# Current_Sensor_Breakout.net
KiCad netlist of a schematic drawn in Altium Designer
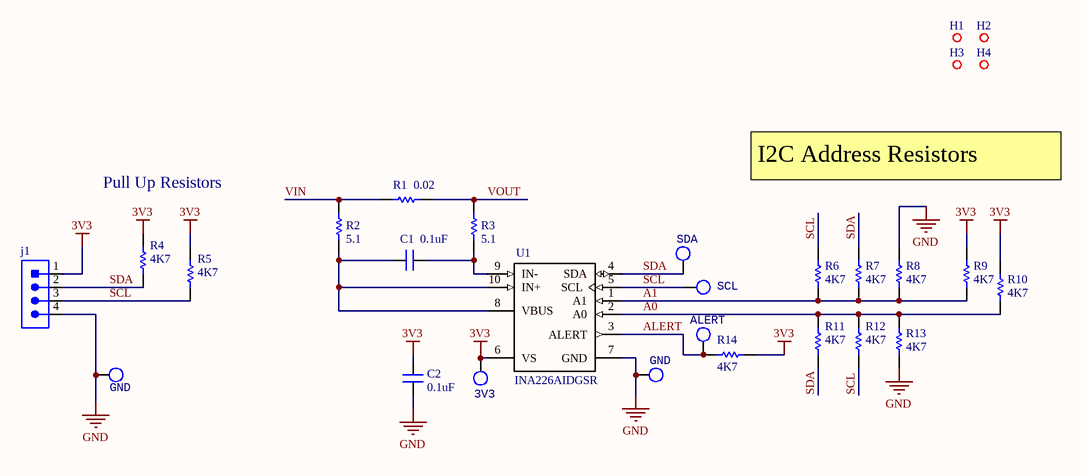
[diagram p0: Current Sensor Breakout.SchDoc]

(export (version "E")
  (design (tool "Eeschema 10.0.6"))
  (components
    (comp (ref "C1")
      (value "0.1uF")
      (footprint "CAPC2012X140N")
      (description "CAP CER 0.1UF 50V X7R 0805")
      (fields (field (name "TOLERANCE") "10%") (field (name "Comment") "CAP_0.1uF_50V_0805"))
      (libsource (lib "UWRT_Schematic_Library_2020") (part "CAP_0.1uF_50V_0805"))
    )
    (comp (ref "C2")
      (value "0.1uF")
      (footprint "CAPC2012X140N")
      (description "CAP CER 0.1UF 50V X7R 0805")
      (fields (field (name "TOLERANCE") "10%") (field (name "Comment") "CAP_0.1uF_50V_0805"))
      (libsource (lib "UWRT_Schematic_Library_2020") (part "CAP_0.1uF_50V_0805"))
    )
    (comp (ref "H1")
      (value "MOUNTING_HOLES")
      (footprint "MOUNTING_HOLE")
      (description "6cm x 6cm")
      (libsource (lib "UWRT_Schematic_Library_2020") (part "MOUNTING_HOLES"))
    )
    (comp (ref "H2")
      (value "MOUNTING_HOLES")
      (footprint "MOUNTING_HOLE")
      (description "6cm x 6cm")
      (libsource (lib "UWRT_Schematic_Library_2020") (part "MOUNTING_HOLES"))
    )
    (comp (ref "H3")
      (value "MOUNTING_HOLES")
      (footprint "MOUNTING_HOLE")
      (description "6cm x 6cm")
      (libsource (lib "UWRT_Schematic_Library_2020") (part "MOUNTING_HOLES"))
    )
    (comp (ref "H4")
      (value "MOUNTING_HOLES")
      (footprint "MOUNTING_HOLE")
      (description "6cm x 6cm")
      (libsource (lib "UWRT_Schematic_Library_2020") (part "MOUNTING_HOLES"))
    )
    (comp (ref "j1")
      (value "CON_4M_TERM")
      (footprint "UWRT_Footprint_Library_2020:1935187")
      (description "TERM BLK 4POS SIDE ENTRY 5MM PCB")
      (fields (field (name "VOLTAGE") "300V"))
      (libsource (lib "UWRT_Schematic_Library_2020") (part "CON_4M_TERM"))
    )
    (comp (ref "R1")
      (value "0.02")
      (footprint "RESC6532X75N")
      (description "RES 0.02 OHM 1% 3W 2512")
      (fields (field (name "Comment") "RES_20m_2512"))
      (libsource (lib "UWRT_Schematic_Library_2020") (part "RES_20m_2512"))
    )
    (comp (ref "R2")
      (value "5.1")
      (footprint "RESC2013X70X40LL20T20")
      (description "RES SMD 5.1 OHM 5% 1/8W 0805")
      (fields (field (name "PART NUMBER") "ERJ-6GEYJ5R1V") (field (name "MANUFACTURER") "Panasonic"))
      (libsource (lib "UWRT_Schematic_Library_2020") (part "RES_5.1_0805"))
    )
    (comp (ref "R3")
      (value "5.1")
      (footprint "RESC2013X70X40LL20T20")
      (description "RES SMD 5.1 OHM 5% 1/8W 0805")
      (fields (field (name "PART NUMBER") "ERJ-6GEYJ5R1V") (field (name "MANUFACTURER") "Panasonic"))
      (libsource (lib "UWRT_Schematic_Library_2020") (part "RES_5.1_0805"))
    )
    (comp (ref "R4")
      (value "4K7")
      (footprint "RESC2012X60N")
      (description "RES SMD 4.7K OHM 5% 1/8W 0805")
      (fields (field (name "TOLERANCE") "5%") (field (name "Comment") "RES_4K7_0805"))
      (libsource (lib "UWRT_Schematic_Library_2020") (part "RES_4K7_0805"))
    )
    (comp (ref "R5")
      (value "4K7")
      (footprint "RESC2012X60N")
      (description "RES SMD 4.7K OHM 5% 1/8W 0805")
      (fields (field (name "TOLERANCE") "5%") (field (name "Comment") "RES_4K7_0805"))
      (libsource (lib "UWRT_Schematic_Library_2020") (part "RES_4K7_0805"))
    )
    (comp (ref "R6")
      (value "4K7")
      (footprint "RESC2012X60N")
      (description "RES SMD 4.7K OHM 5% 1/8W 0805")
      (fields (field (name "TOLERANCE") "5%") (field (name "Comment") "RES_4K7_0805"))
      (libsource (lib "UWRT_Schematic_Library_2020") (part "RES_4K7_0805"))
    )
    (comp (ref "R7")
      (value "4K7")
      (footprint "RESC2012X60N")
      (description "RES SMD 4.7K OHM 5% 1/8W 0805")
      (fields (field (name "TOLERANCE") "5%") (field (name "Comment") "RES_4K7_0805"))
      (libsource (lib "UWRT_Schematic_Library_2020") (part "RES_4K7_0805"))
    )
    (comp (ref "R8")
      (value "4K7")
      (footprint "RESC2012X60N")
      (description "RES SMD 4.7K OHM 5% 1/8W 0805")
      (fields (field (name "TOLERANCE") "5%") (field (name "Comment") "RES_4K7_0805"))
      (libsource (lib "UWRT_Schematic_Library_2020") (part "RES_4K7_0805"))
    )
    (comp (ref "R9")
      (value "4K7")
      (footprint "RESC2012X60N")
      (description "RES SMD 4.7K OHM 5% 1/8W 0805")
      (fields (field (name "TOLERANCE") "5%") (field (name "Comment") "RES_4K7_0805"))
      (libsource (lib "UWRT_Schematic_Library_2020") (part "RES_4K7_0805"))
    )
    (comp (ref "R10")
      (value "4K7")
      (footprint "RESC2012X60N")
      (description "RES SMD 4.7K OHM 5% 1/8W 0805")
      (fields (field (name "TOLERANCE") "5%") (field (name "Comment") "RES_4K7_0805"))
      (libsource (lib "UWRT_Schematic_Library_2020") (part "RES_4K7_0805"))
    )
    (comp (ref "R11")
      (value "4K7")
      (footprint "RESC2012X60N")
      (description "RES SMD 4.7K OHM 5% 1/8W 0805")
      (fields (field (name "TOLERANCE") "5%") (field (name "Comment") "RES_4K7_0805"))
      (libsource (lib "UWRT_Schematic_Library_2020") (part "RES_4K7_0805"))
    )
    (comp (ref "R12")
      (value "4K7")
      (footprint "RESC2012X60N")
      (description "RES SMD 4.7K OHM 5% 1/8W 0805")
      (fields (field (name "TOLERANCE") "5%") (field (name "Comment") "RES_4K7_0805"))
      (libsource (lib "UWRT_Schematic_Library_2020") (part "RES_4K7_0805"))
    )
    (comp (ref "R13")
      (value "4K7")
      (footprint "RESC2012X60N")
      (description "RES SMD 4.7K OHM 5% 1/8W 0805")
      (fields (field (name "TOLERANCE") "5%") (field (name "Comment") "RES_4K7_0805"))
      (libsource (lib "UWRT_Schematic_Library_2020") (part "RES_4K7_0805"))
    )
    (comp (ref "R14")
      (value "4K7")
      (footprint "RESC2012X60N")
      (description "RES SMD 4.7K OHM 5% 1/8W 0805")
      (fields (field (name "TOLERANCE") "5%") (field (name "Comment") "RES_4K7_0805"))
      (libsource (lib "UWRT_Schematic_Library_2020") (part "RES_4K7_0805"))
    )
    (comp (ref "TP1")
      (value "SDA")
      (footprint "TESTPOINT_LOOP")
      (description "Loop testpoint through-hole pad")
      (fields (field (name "MANUFACTURER") "Keystone Electronics"))
      (libsource (lib "UWRT_Schematic_Library_2020") (part "TESTPOINT_LOOP"))
    )
    (comp (ref "TP2")
      (value "SCL")
      (footprint "TESTPOINT_LOOP")
      (description "Loop testpoint through-hole pad")
      (fields (field (name "MANUFACTURER") "Keystone Electronics"))
      (libsource (lib "UWRT_Schematic_Library_2020") (part "TESTPOINT_LOOP"))
    )
    (comp (ref "TP3")
      (value "ALERT")
      (footprint "TESTPOINT_LOOP")
      (description "Loop testpoint through-hole pad")
      (fields (field (name "MANUFACTURER") "Keystone Electronics"))
      (libsource (lib "UWRT_Schematic_Library_2020") (part "TESTPOINT_LOOP"))
    )
    (comp (ref "TP4")
      (value "GND")
      (footprint "TESTPOINT_LOOP")
      (description "Loop testpoint through-hole pad")
      (fields (field (name "MANUFACTURER") "Keystone Electronics"))
      (libsource (lib "UWRT_Schematic_Library_2020") (part "TESTPOINT_LOOP"))
    )
    (comp (ref "TP5")
      (value "3V3")
      (footprint "TESTPOINT_LOOP")
      (description "Loop testpoint through-hole pad")
      (fields (field (name "MANUFACTURER") "Keystone Electronics"))
      (libsource (lib "UWRT_Schematic_Library_2020") (part "TESTPOINT_LOOP"))
    )
    (comp (ref "TP6")
      (value "GND")
      (footprint "TESTPOINT_LOOP")
      (description "Loop testpoint through-hole pad")
      (libsource (lib "UWRT_Schematic_Library_2020") (part "TESTPOINT_LOOP"))
    )
    (comp (ref "U1")
      (value "INA226AIDGSR")
      (footprint "INA226AIDGSR")
      (description "IC MONITOR PWR/CURR BIDIR 10MSOP")
      (fields (field (name "MF") "Texas Instruments"))
      (libsource (lib "UWRT_Schematic_Library_2020") (part "INA226AIDGSR"))
    )
  )
  (nets
    (net (code "1") (name "/A0") (class "Default")
      (node (ref "R10") (pin "1") (pinfunction "1_1") (pintype "passive"))
      (node (ref "R11") (pin "1") (pinfunction "1_1") (pintype "passive"))
      (node (ref "R12") (pin "1") (pinfunction "1_1") (pintype "passive"))
      (node (ref "R13") (pin "1") (pinfunction "1_1") (pintype "passive"))
      (node (ref "U1") (pin "2") (pinfunction "A0_2") (pintype "input"))
    )
    (net (code "2") (name "/A1") (class "Default")
      (node (ref "R6") (pin "1") (pinfunction "1_1") (pintype "passive"))
      (node (ref "R7") (pin "1") (pinfunction "1_1") (pintype "passive"))
      (node (ref "R8") (pin "1") (pinfunction "1_1") (pintype "passive"))
      (node (ref "R9") (pin "1") (pinfunction "1_1") (pintype "passive"))
      (node (ref "U1") (pin "1") (pinfunction "A1_1") (pintype "input"))
    )
    (net (code "3") (name "/ALERT") (class "Default")
      (node (ref "R14") (pin "1") (pinfunction "1_1") (pintype "passive"))
      (node (ref "TP3") (pin "1") (pintype "passive"))
      (node (ref "U1") (pin "3") (pinfunction "ALERT_3") (pintype "output"))
    )
    (net (code "4") (name "/SCL") (class "Default")
      (node (ref "R12") (pin "2") (pinfunction "2_2") (pintype "passive"))
      (node (ref "R5") (pin "2") (pinfunction "2_2") (pintype "passive"))
      (node (ref "R6") (pin "2") (pinfunction "2_2") (pintype "passive"))
      (node (ref "TP2") (pin "1") (pintype "passive"))
      (node (ref "U1") (pin "5") (pinfunction "SCL_5") (pintype "input"))
      (node (ref "j1") (pin "3") (pinfunction "3_3") (pintype "passive"))
    )
    (net (code "5") (name "/SDA") (class "Default")
      (node (ref "R11") (pin "2") (pinfunction "2_2") (pintype "passive"))
      (node (ref "R4") (pin "2") (pinfunction "2_2") (pintype "passive"))
      (node (ref "R7") (pin "2") (pinfunction "2_2") (pintype "passive"))
      (node (ref "TP1") (pin "1") (pintype "passive"))
      (node (ref "U1") (pin "4") (pinfunction "SDA_4") (pintype "bidirectional"))
      (node (ref "j1") (pin "2") (pinfunction "2_2") (pintype "passive"))
    )
    (net (code "6") (name "/VIN") (class "Default")
      (node (ref "R1") (pin "1") (pinfunction "1_1") (pintype "passive"))
      (node (ref "R2") (pin "2") (pinfunction "2_2") (pintype "passive"))
    )
    (net (code "7") (name "/VOUT") (class "Default")
      (node (ref "R1") (pin "2") (pinfunction "2_2") (pintype "passive"))
      (node (ref "R3") (pin "2") (pinfunction "2_2") (pintype "passive"))
    )
    (net (code "8") (name "3V3") (class "Default")
      (node (ref "C2") (pin "2") (pinfunction "2_2") (pintype "passive"))
      (node (ref "R10") (pin "2") (pinfunction "2_2") (pintype "passive"))
      (node (ref "R14") (pin "2") (pinfunction "2_2") (pintype "passive"))
      (node (ref "R4") (pin "1") (pinfunction "1_1") (pintype "passive"))
      (node (ref "R5") (pin "1") (pinfunction "1_1") (pintype "passive"))
      (node (ref "R9") (pin "2") (pinfunction "2_2") (pintype "passive"))
      (node (ref "TP5") (pin "1") (pintype "passive"))
      (node (ref "U1") (pin "6") (pinfunction "VS_6") (pintype "power_in"))
      (node (ref "j1") (pin "1") (pinfunction "1_1") (pintype "passive"))
    )
    (net (code "9") (name "GND") (class "Default")
      (node (ref "C2") (pin "1") (pinfunction "1_1") (pintype "passive"))
      (node (ref "R13") (pin "2") (pinfunction "2_2") (pintype "passive"))
      (node (ref "R8") (pin "2") (pinfunction "2_2") (pintype "passive"))
      (node (ref "TP4") (pin "1") (pintype "passive"))
      (node (ref "TP6") (pin "1") (pintype "passive"))
      (node (ref "U1") (pin "7") (pinfunction "GND_7") (pintype "power_in"))
      (node (ref "j1") (pin "4") (pinfunction "4_4") (pintype "passive"))
    )
    (net (code "10") (name "Net-(U1-IN+)") (class "Default")
      (node (ref "C1") (pin "1") (pinfunction "1_1") (pintype "passive"))
      (node (ref "R2") (pin "1") (pinfunction "1_1") (pintype "passive"))
      (node (ref "U1") (pin "10") (pinfunction "IN+_10") (pintype "input"))
      (node (ref "U1") (pin "8") (pinfunction "VBUS_8") (pintype "power_in"))
    )
    (net (code "11") (name "Net-(U1-IN-)") (class "Default")
      (node (ref "C1") (pin "2") (pinfunction "2_2") (pintype "passive"))
      (node (ref "R3") (pin "1") (pinfunction "1_1") (pintype "passive"))
      (node (ref "U1") (pin "9") (pinfunction "IN-_9") (pintype "input"))
    )
  )
)
